# FX3_Explorer_Breakout_RevC.net
KiCad netlist of a schematic drawn in EAGLE
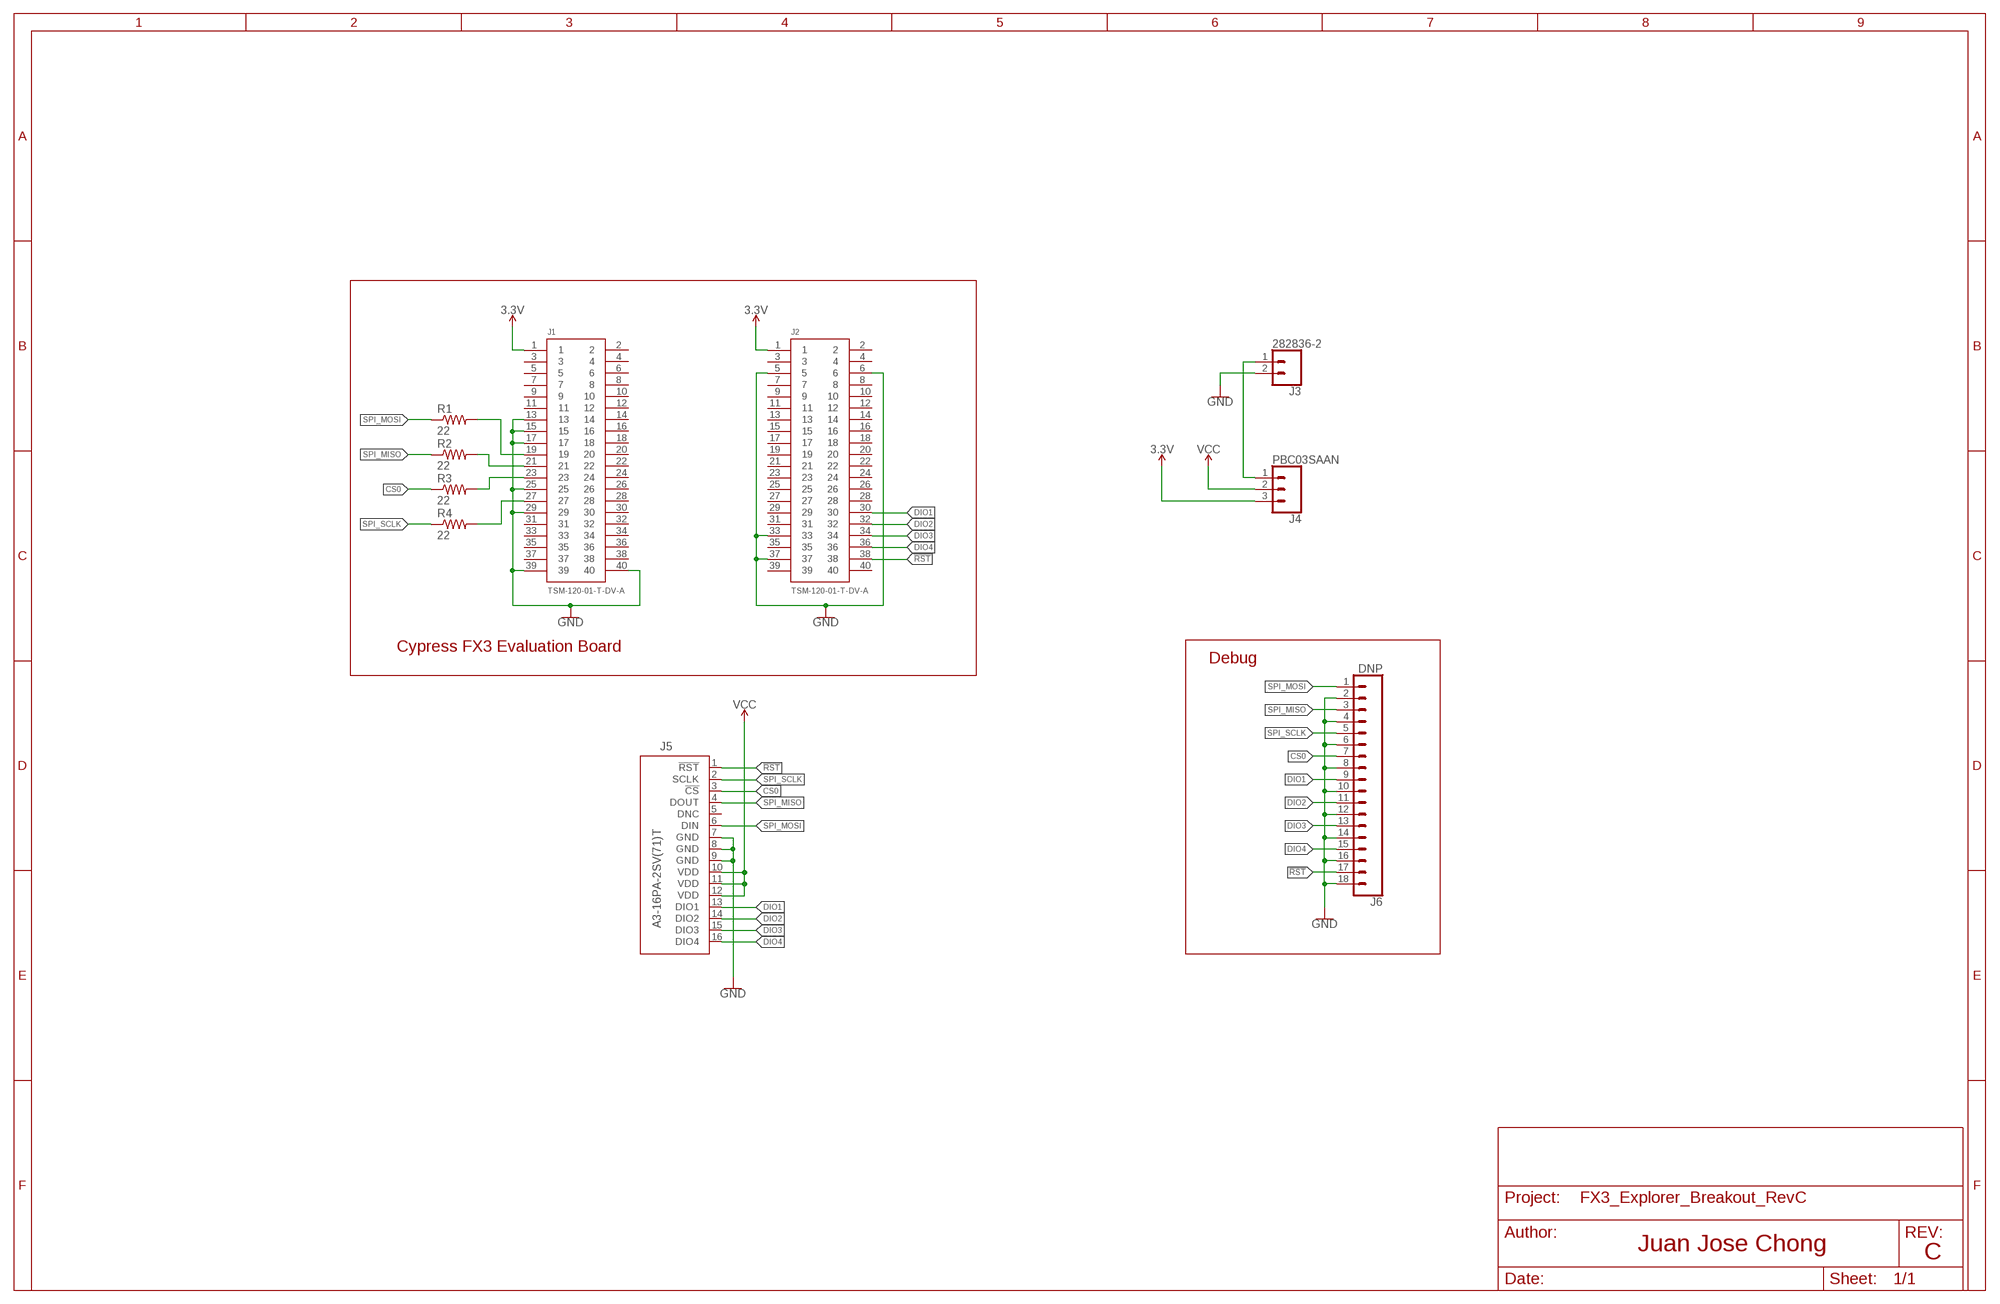
[diagram p0: schematic, sheet 1]

(export (version "E")
  (design (tool "Eeschema 10.0.6"))
  (components
    (comp (ref "J1")
      (value "TSM-120-01-T-DV-A")
      (footprint "eagle-import:TSM-120-XX-XXX-D")
      (libsource (lib "eagle-import") (part "TSM-120-XX-XXX-DV"))
    )
    (comp (ref "J2")
      (value "TSM-120-01-T-DV-A")
      (footprint "eagle-import:TSM-120-XX-XXX-D")
      (libsource (lib "eagle-import") (part "TSM-120-XX-XXX-DV"))
    )
    (comp (ref "J3")
      (value "282836-2")
      (footprint "eagle-import:SCREWTERMINAL-5MM-2")
      (libsource (lib "eagle-import") (part "CONN_025MM"))
    )
    (comp (ref "J4")
      (value "PBC03SAAN")
      (footprint "eagle-import:1X03")
      (libsource (lib "eagle-import") (part "CONN_03"))
    )
    (comp (ref "J5")
      (value "A3-16PA-2SV(71)T")
      (footprint "eagle-import:A3-16PA-2SV(71)-TOP")
      (fields (field (name "PARTNO") "A3-16PA-2SV(71)"))
      (libsource (lib "eagle-import") (part "A3-16PA-2SV(71)T"))
    )
    (comp (ref "J6")
      (value "DNP")
      (footprint "eagle-import:1X18")
      (libsource (lib "eagle-import") (part "CONN_18SILK"))
    )
    (comp (ref "R1")
      (value "22")
      (footprint "eagle-import:R0603")
      (fields (field (name "PARTNO") "RC0603FR-0722RL"))
      (libsource (lib "eagle-import") (part "R-US_R0603"))
    )
    (comp (ref "R2")
      (value "22")
      (footprint "eagle-import:R0603")
      (fields (field (name "PARTNO") "RC0603FR-0722RL"))
      (libsource (lib "eagle-import") (part "R-US_R0603"))
    )
    (comp (ref "R3")
      (value "22")
      (footprint "eagle-import:R0603")
      (fields (field (name "PARTNO") "RC0603FR-0722RL"))
      (libsource (lib "eagle-import") (part "R-US_R0603"))
    )
    (comp (ref "R4")
      (value "22")
      (footprint "eagle-import:R0603")
      (fields (field (name "PARTNO") "RC0603FR-0722RL"))
      (libsource (lib "eagle-import") (part "R-US_R0603"))
    )
  )
  (nets
    (net (code "1") (name "/~{RST}") (class "Default")
      (node (ref "J2") (pin "38") (pinfunction "38_38") (pintype "bidirectional"))
      (node (ref "J5") (pin "1") (pinfunction "~{RST}_1") (pintype "bidirectional"))
      (node (ref "J6") (pin "17") (pinfunction "17_17") (pintype "passive"))
    )
    (net (code "2") (name "3.3V") (class "Default")
      (node (ref "J1") (pin "1") (pinfunction "1_1") (pintype "bidirectional"))
      (node (ref "J2") (pin "1") (pinfunction "1_1") (pintype "bidirectional"))
      (node (ref "J4") (pin "3") (pinfunction "3_3") (pintype "passive"))
    )
    (net (code "3") (name "CS0") (class "Default")
      (node (ref "J5") (pin "3") (pinfunction "~{CS}_3") (pintype "bidirectional"))
      (node (ref "J6") (pin "7") (pinfunction "7_7") (pintype "passive"))
      (node (ref "R3") (pin "1") (pinfunction "1_1") (pintype "passive"))
    )
    (net (code "4") (name "DIO1") (class "Default")
      (node (ref "J2") (pin "30") (pinfunction "30_30") (pintype "bidirectional"))
      (node (ref "J5") (pin "13") (pinfunction "DIO1_13") (pintype "bidirectional"))
      (node (ref "J6") (pin "9") (pinfunction "9_9") (pintype "passive"))
    )
    (net (code "5") (name "DIO2") (class "Default")
      (node (ref "J2") (pin "32") (pinfunction "32_32") (pintype "bidirectional"))
      (node (ref "J5") (pin "14") (pinfunction "DIO2_14") (pintype "bidirectional"))
      (node (ref "J6") (pin "11") (pinfunction "11_11") (pintype "passive"))
    )
    (net (code "6") (name "DIO3") (class "Default")
      (node (ref "J2") (pin "34") (pinfunction "34_34") (pintype "bidirectional"))
      (node (ref "J5") (pin "15") (pinfunction "DIO3_15") (pintype "bidirectional"))
      (node (ref "J6") (pin "13") (pinfunction "13_13") (pintype "passive"))
    )
    (net (code "7") (name "DIO4") (class "Default")
      (node (ref "J2") (pin "36") (pinfunction "36_36") (pintype "bidirectional"))
      (node (ref "J5") (pin "16") (pinfunction "DIO4_16") (pintype "bidirectional"))
      (node (ref "J6") (pin "15") (pinfunction "15_15") (pintype "passive"))
    )
    (net (code "8") (name "GND") (class "Default")
      (node (ref "J1") (pin "13") (pinfunction "13_13") (pintype "bidirectional"))
      (node (ref "J1") (pin "15") (pinfunction "15_15") (pintype "bidirectional"))
      (node (ref "J1") (pin "17") (pinfunction "17_17") (pintype "bidirectional"))
      (node (ref "J1") (pin "25") (pinfunction "25_25") (pintype "bidirectional"))
      (node (ref "J1") (pin "29") (pinfunction "29_29") (pintype "bidirectional"))
      (node (ref "J1") (pin "39") (pinfunction "39_39") (pintype "bidirectional"))
      (node (ref "J1") (pin "40") (pinfunction "40_40") (pintype "bidirectional"))
      (node (ref "J2") (pin "33") (pinfunction "33_33") (pintype "bidirectional"))
      (node (ref "J2") (pin "37") (pinfunction "37_37") (pintype "bidirectional"))
      (node (ref "J2") (pin "5") (pinfunction "5_5") (pintype "bidirectional"))
      (node (ref "J2") (pin "6") (pinfunction "6_6") (pintype "bidirectional"))
      (node (ref "J3") (pin "2") (pinfunction "2_2") (pintype "passive"))
      (node (ref "J5") (pin "7") (pinfunction "GND_7") (pintype "bidirectional"))
      (node (ref "J5") (pin "8") (pinfunction "GND_8") (pintype "bidirectional"))
      (node (ref "J5") (pin "9") (pinfunction "GND_9") (pintype "bidirectional"))
      (node (ref "J6") (pin "10") (pinfunction "10_10") (pintype "passive"))
      (node (ref "J6") (pin "12") (pinfunction "12_12") (pintype "passive"))
      (node (ref "J6") (pin "14") (pinfunction "14_14") (pintype "passive"))
      (node (ref "J6") (pin "16") (pinfunction "16_16") (pintype "passive"))
      (node (ref "J6") (pin "18") (pinfunction "18_18") (pintype "passive"))
      (node (ref "J6") (pin "2") (pinfunction "2_2") (pintype "passive"))
      (node (ref "J6") (pin "4") (pinfunction "4_4") (pintype "passive"))
      (node (ref "J6") (pin "6") (pinfunction "6_6") (pintype "passive"))
      (node (ref "J6") (pin "8") (pinfunction "8_8") (pintype "passive"))
    )
    (net (code "9") (name "Net-(J1-Pad19)") (class "Default")
      (node (ref "J1") (pin "19") (pinfunction "19_19") (pintype "bidirectional"))
      (node (ref "R1") (pin "2") (pinfunction "2_2") (pintype "passive"))
    )
    (net (code "10") (name "Net-(J1-Pad21)") (class "Default")
      (node (ref "J1") (pin "21") (pinfunction "21_21") (pintype "bidirectional"))
      (node (ref "R2") (pin "2") (pinfunction "2_2") (pintype "passive"))
    )
    (net (code "11") (name "Net-(J1-Pad23)") (class "Default")
      (node (ref "J1") (pin "23") (pinfunction "23_23") (pintype "bidirectional"))
      (node (ref "R3") (pin "2") (pinfunction "2_2") (pintype "passive"))
    )
    (net (code "12") (name "Net-(J1-Pad27)") (class "Default")
      (node (ref "J1") (pin "27") (pinfunction "27_27") (pintype "bidirectional"))
      (node (ref "R4") (pin "2") (pinfunction "2_2") (pintype "passive"))
    )
    (net (code "13") (name "Net-(J3-Pad1)") (class "Default")
      (node (ref "J3") (pin "1") (pinfunction "1_1") (pintype "passive"))
      (node (ref "J4") (pin "1") (pinfunction "1_1") (pintype "passive"))
    )
    (net (code "14") (name "SPI_MISO") (class "Default")
      (node (ref "J5") (pin "4") (pinfunction "DOUT_4") (pintype "bidirectional"))
      (node (ref "J6") (pin "3") (pinfunction "3_3") (pintype "passive"))
      (node (ref "R2") (pin "1") (pinfunction "1_1") (pintype "passive"))
    )
    (net (code "15") (name "SPI_MOSI") (class "Default")
      (node (ref "J5") (pin "6") (pinfunction "DIN_6") (pintype "bidirectional"))
      (node (ref "J6") (pin "1") (pinfunction "1_1") (pintype "passive"))
      (node (ref "R1") (pin "1") (pinfunction "1_1") (pintype "passive"))
    )
    (net (code "16") (name "SPI_SCLK") (class "Default")
      (node (ref "J5") (pin "2") (pinfunction "SCLK_2") (pintype "bidirectional"))
      (node (ref "J6") (pin "5") (pinfunction "5_5") (pintype "passive"))
      (node (ref "R4") (pin "1") (pinfunction "1_1") (pintype "passive"))
    )
    (net (code "17") (name "VCC") (class "Default")
      (node (ref "J4") (pin "2") (pinfunction "2_2") (pintype "passive"))
      (node (ref "J5") (pin "10") (pinfunction "VDD_10") (pintype "bidirectional"))
      (node (ref "J5") (pin "11") (pinfunction "VDD_11") (pintype "bidirectional"))
      (node (ref "J5") (pin "12") (pinfunction "VDD_12") (pintype "bidirectional"))
    )
    (net (code "18") (name "unconnected-(J1-Pad2)") (class "Default")
      (node (ref "J1") (pin "2") (pinfunction "2_2") (pintype "bidirectional"))
    )
    (net (code "19") (name "unconnected-(J1-Pad3)") (class "Default")
      (node (ref "J1") (pin "3") (pinfunction "3_3") (pintype "bidirectional"))
    )
    (net (code "20") (name "unconnected-(J1-Pad4)") (class "Default")
      (node (ref "J1") (pin "4") (pinfunction "4_4") (pintype "bidirectional"))
    )
    (net (code "21") (name "unconnected-(J1-Pad5)") (class "Default")
      (node (ref "J1") (pin "5") (pinfunction "5_5") (pintype "bidirectional"))
    )
    (net (code "22") (name "unconnected-(J1-Pad6)") (class "Default")
      (node (ref "J1") (pin "6") (pinfunction "6_6") (pintype "bidirectional"))
    )
    (net (code "23") (name "unconnected-(J1-Pad7)") (class "Default")
      (node (ref "J1") (pin "7") (pinfunction "7_7") (pintype "bidirectional"))
    )
    (net (code "24") (name "unconnected-(J1-Pad8)") (class "Default")
      (node (ref "J1") (pin "8") (pinfunction "8_8") (pintype "bidirectional"))
    )
    (net (code "25") (name "unconnected-(J1-Pad9)") (class "Default")
      (node (ref "J1") (pin "9") (pinfunction "9_9") (pintype "bidirectional"))
    )
    (net (code "26") (name "unconnected-(J1-Pad10)") (class "Default")
      (node (ref "J1") (pin "10") (pinfunction "10_10") (pintype "bidirectional"))
    )
    (net (code "27") (name "unconnected-(J1-Pad11)") (class "Default")
      (node (ref "J1") (pin "11") (pinfunction "11_11") (pintype "bidirectional"))
    )
    (net (code "28") (name "unconnected-(J1-Pad12)") (class "Default")
      (node (ref "J1") (pin "12") (pinfunction "12_12") (pintype "bidirectional"))
    )
    (net (code "29") (name "unconnected-(J1-Pad14)") (class "Default")
      (node (ref "J1") (pin "14") (pinfunction "14_14") (pintype "bidirectional"))
    )
    (net (code "30") (name "unconnected-(J1-Pad16)") (class "Default")
      (node (ref "J1") (pin "16") (pinfunction "16_16") (pintype "bidirectional"))
    )
    (net (code "31") (name "unconnected-(J1-Pad18)") (class "Default")
      (node (ref "J1") (pin "18") (pinfunction "18_18") (pintype "bidirectional"))
    )
    (net (code "32") (name "unconnected-(J1-Pad20)") (class "Default")
      (node (ref "J1") (pin "20") (pinfunction "20_20") (pintype "bidirectional"))
    )
    (net (code "33") (name "unconnected-(J1-Pad22)") (class "Default")
      (node (ref "J1") (pin "22") (pinfunction "22_22") (pintype "bidirectional"))
    )
    (net (code "34") (name "unconnected-(J1-Pad24)") (class "Default")
      (node (ref "J1") (pin "24") (pinfunction "24_24") (pintype "bidirectional"))
    )
    (net (code "35") (name "unconnected-(J1-Pad26)") (class "Default")
      (node (ref "J1") (pin "26") (pinfunction "26_26") (pintype "bidirectional"))
    )
    (net (code "36") (name "unconnected-(J1-Pad28)") (class "Default")
      (node (ref "J1") (pin "28") (pinfunction "28_28") (pintype "bidirectional"))
    )
    (net (code "37") (name "unconnected-(J1-Pad30)") (class "Default")
      (node (ref "J1") (pin "30") (pinfunction "30_30") (pintype "bidirectional"))
    )
    (net (code "38") (name "unconnected-(J1-Pad31)") (class "Default")
      (node (ref "J1") (pin "31") (pinfunction "31_31") (pintype "bidirectional"))
    )
    (net (code "39") (name "unconnected-(J1-Pad32)") (class "Default")
      (node (ref "J1") (pin "32") (pinfunction "32_32") (pintype "bidirectional"))
    )
    (net (code "40") (name "unconnected-(J1-Pad33)") (class "Default")
      (node (ref "J1") (pin "33") (pinfunction "33_33") (pintype "bidirectional"))
    )
    (net (code "41") (name "unconnected-(J1-Pad34)") (class "Default")
      (node (ref "J1") (pin "34") (pinfunction "34_34") (pintype "bidirectional"))
    )
    (net (code "42") (name "unconnected-(J1-Pad35)") (class "Default")
      (node (ref "J1") (pin "35") (pinfunction "35_35") (pintype "bidirectional"))
    )
    (net (code "43") (name "unconnected-(J1-Pad36)") (class "Default")
      (node (ref "J1") (pin "36") (pinfunction "36_36") (pintype "bidirectional"))
    )
    (net (code "44") (name "unconnected-(J1-Pad37)") (class "Default")
      (node (ref "J1") (pin "37") (pinfunction "37_37") (pintype "bidirectional"))
    )
    (net (code "45") (name "unconnected-(J1-Pad38)") (class "Default")
      (node (ref "J1") (pin "38") (pinfunction "38_38") (pintype "bidirectional"))
    )
    (net (code "46") (name "unconnected-(J2-Pad2)") (class "Default")
      (node (ref "J2") (pin "2") (pinfunction "2_2") (pintype "bidirectional"))
    )
    (net (code "47") (name "unconnected-(J2-Pad3)") (class "Default")
      (node (ref "J2") (pin "3") (pinfunction "3_3") (pintype "bidirectional"))
    )
    (net (code "48") (name "unconnected-(J2-Pad4)") (class "Default")
      (node (ref "J2") (pin "4") (pinfunction "4_4") (pintype "bidirectional"))
    )
    (net (code "49") (name "unconnected-(J2-Pad7)") (class "Default")
      (node (ref "J2") (pin "7") (pinfunction "7_7") (pintype "bidirectional"))
    )
    (net (code "50") (name "unconnected-(J2-Pad8)") (class "Default")
      (node (ref "J2") (pin "8") (pinfunction "8_8") (pintype "bidirectional"))
    )
    (net (code "51") (name "unconnected-(J2-Pad9)") (class "Default")
      (node (ref "J2") (pin "9") (pinfunction "9_9") (pintype "bidirectional"))
    )
    (net (code "52") (name "unconnected-(J2-Pad10)") (class "Default")
      (node (ref "J2") (pin "10") (pinfunction "10_10") (pintype "bidirectional"))
    )
    (net (code "53") (name "unconnected-(J2-Pad11)") (class "Default")
      (node (ref "J2") (pin "11") (pinfunction "11_11") (pintype "bidirectional"))
    )
    (net (code "54") (name "unconnected-(J2-Pad12)") (class "Default")
      (node (ref "J2") (pin "12") (pinfunction "12_12") (pintype "bidirectional"))
    )
    (net (code "55") (name "unconnected-(J2-Pad13)") (class "Default")
      (node (ref "J2") (pin "13") (pinfunction "13_13") (pintype "bidirectional"))
    )
    (net (code "56") (name "unconnected-(J2-Pad14)") (class "Default")
      (node (ref "J2") (pin "14") (pinfunction "14_14") (pintype "bidirectional"))
    )
    (net (code "57") (name "unconnected-(J2-Pad15)") (class "Default")
      (node (ref "J2") (pin "15") (pinfunction "15_15") (pintype "bidirectional"))
    )
    (net (code "58") (name "unconnected-(J2-Pad16)") (class "Default")
      (node (ref "J2") (pin "16") (pinfunction "16_16") (pintype "bidirectional"))
    )
    (net (code "59") (name "unconnected-(J2-Pad17)") (class "Default")
      (node (ref "J2") (pin "17") (pinfunction "17_17") (pintype "bidirectional"))
    )
    (net (code "60") (name "unconnected-(J2-Pad18)") (class "Default")
      (node (ref "J2") (pin "18") (pinfunction "18_18") (pintype "bidirectional"))
    )
    (net (code "61") (name "unconnected-(J2-Pad19)") (class "Default")
      (node (ref "J2") (pin "19") (pinfunction "19_19") (pintype "bidirectional"))
    )
    (net (code "62") (name "unconnected-(J2-Pad20)") (class "Default")
      (node (ref "J2") (pin "20") (pinfunction "20_20") (pintype "bidirectional"))
    )
    (net (code "63") (name "unconnected-(J2-Pad21)") (class "Default")
      (node (ref "J2") (pin "21") (pinfunction "21_21") (pintype "bidirectional"))
    )
    (net (code "64") (name "unconnected-(J2-Pad22)") (class "Default")
      (node (ref "J2") (pin "22") (pinfunction "22_22") (pintype "bidirectional"))
    )
    (net (code "65") (name "unconnected-(J2-Pad23)") (class "Default")
      (node (ref "J2") (pin "23") (pinfunction "23_23") (pintype "bidirectional"))
    )
    (net (code "66") (name "unconnected-(J2-Pad24)") (class "Default")
      (node (ref "J2") (pin "24") (pinfunction "24_24") (pintype "bidirectional"))
    )
    (net (code "67") (name "unconnected-(J2-Pad25)") (class "Default")
      (node (ref "J2") (pin "25") (pinfunction "25_25") (pintype "bidirectional"))
    )
    (net (code "68") (name "unconnected-(J2-Pad26)") (class "Default")
      (node (ref "J2") (pin "26") (pinfunction "26_26") (pintype "bidirectional"))
    )
    (net (code "69") (name "unconnected-(J2-Pad27)") (class "Default")
      (node (ref "J2") (pin "27") (pinfunction "27_27") (pintype "bidirectional"))
    )
    (net (code "70") (name "unconnected-(J2-Pad28)") (class "Default")
      (node (ref "J2") (pin "28") (pinfunction "28_28") (pintype "bidirectional"))
    )
    (net (code "71") (name "unconnected-(J2-Pad29)") (class "Default")
      (node (ref "J2") (pin "29") (pinfunction "29_29") (pintype "bidirectional"))
    )
    (net (code "72") (name "unconnected-(J2-Pad31)") (class "Default")
      (node (ref "J2") (pin "31") (pinfunction "31_31") (pintype "bidirectional"))
    )
    (net (code "73") (name "unconnected-(J2-Pad35)") (class "Default")
      (node (ref "J2") (pin "35") (pinfunction "35_35") (pintype "bidirectional"))
    )
    (net (code "74") (name "unconnected-(J2-Pad39)") (class "Default")
      (node (ref "J2") (pin "39") (pinfunction "39_39") (pintype "bidirectional"))
    )
    (net (code "75") (name "unconnected-(J2-Pad40)") (class "Default")
      (node (ref "J2") (pin "40") (pinfunction "40_40") (pintype "bidirectional"))
    )
    (net (code "76") (name "unconnected-(J5-DNC-Pad5)") (class "Default")
      (node (ref "J5") (pin "5") (pinfunction "DNC_5") (pintype "bidirectional"))
    )
  )
)
